# Kanaloa_v2_0_0_Motor.net
KiCad netlist of a schematic drawn in Altium Designer
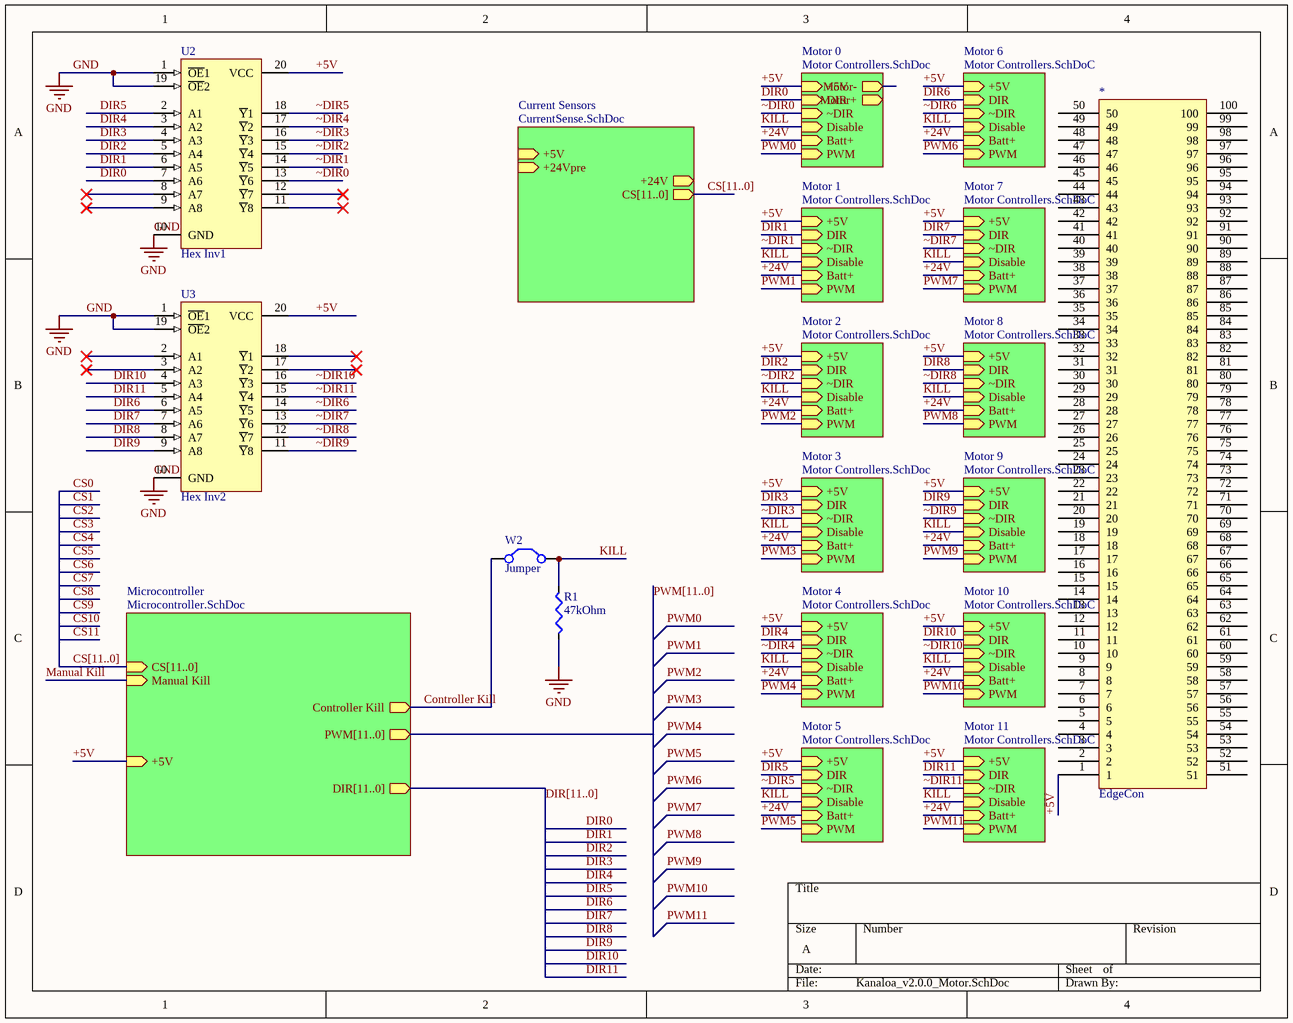
[diagram p0: Kanaloa_v2.0.0_Motor.SchDoc]

(export (version "E")
  (design (tool "Eeschema 10.0.6"))
  (components
    (comp (ref "*")
      (value "EdgeCon")
      (footprint "5645235-3 CON")
      (libsource (lib "Kanaloa_v2.0.0_Motor") (part "EdgeCon"))
    )
    (comp (ref "R1")
      (value "47kOhm")
      (footprint "R 1210 (3225) RESISTOR")
      (description "Resistor")
      (libsource (lib "PassiveComponents") (part "Resistor"))
    )
    (comp (ref "U2")
      (value "Hex Inv1")
      (footprint "DW020_N")
      (description "Octal Buffer and Line Driver with 3-State Outputs")
      (fields (field (name "PUBLISHER") "Altium Limited"))
      (libsource (lib "TI Logic Buffer Line Driver") (part "SN74HCT540DW"))
    )
    (comp (ref "U3")
      (value "Hex Inv2")
      (footprint "DW020_N")
      (description "Octal Buffer and Line Driver with 3-State Outputs")
      (fields (field (name "PUBLISHER") "Altium Limited"))
      (libsource (lib "TI Logic Buffer Line Driver") (part "SN74HCT540DW"))
    )
    (comp (ref "W2")
      (value "Jumper")
      (footprint "RAD-0.2")
      (description "Jumper Wire")
      (fields (field (name "PUBLISHER") "Altium Limited"))
      (libsource (lib "Miscellaneous Devices") (part "Jumper"))
    )
  )
  (nets
    (net (code "1") (name "/+5V") (class "Default")
      (node (ref "*") (pin "1") (pinfunction "1_1") (pintype "passive"))
      (node (ref "U2") (pin "20") (pinfunction "VCC_20") (pintype "power_in"))
      (node (ref "U3") (pin "20") (pinfunction "VCC_20") (pintype "power_in"))
    )
    (net (code "19") (name "/Controller Kill") (class "Default")
      (node (ref "W2") (pin "1") (pinfunction "C1_1") (pintype "passive"))
    )
    (net (code "20") (name "/DIR0") (class "Default")
      (node (ref "U2") (pin "7") (pinfunction "A6_7") (pintype "input"))
    )
    (net (code "21") (name "/DIR1") (class "Default")
      (node (ref "U2") (pin "6") (pinfunction "A5_6") (pintype "input"))
    )
    (net (code "22") (name "/DIR2") (class "Default")
      (node (ref "U2") (pin "5") (pinfunction "A4_5") (pintype "input"))
    )
    (net (code "23") (name "/DIR3") (class "Default")
      (node (ref "U2") (pin "4") (pinfunction "A3_4") (pintype "input"))
    )
    (net (code "24") (name "/DIR4") (class "Default")
      (node (ref "U2") (pin "3") (pinfunction "A2_3") (pintype "input"))
    )
    (net (code "25") (name "/DIR5") (class "Default")
      (node (ref "U2") (pin "2") (pinfunction "A1_2") (pintype "input"))
    )
    (net (code "26") (name "/DIR6") (class "Default")
      (node (ref "U3") (pin "6") (pinfunction "A5_6") (pintype "input"))
    )
    (net (code "27") (name "/DIR7") (class "Default")
      (node (ref "U3") (pin "7") (pinfunction "A6_7") (pintype "input"))
    )
    (net (code "28") (name "/DIR8") (class "Default")
      (node (ref "U3") (pin "8") (pinfunction "A7_8") (pintype "input"))
    )
    (net (code "29") (name "/DIR9") (class "Default")
      (node (ref "U3") (pin "9") (pinfunction "A8_9") (pintype "input"))
    )
    (net (code "30") (name "/DIR10") (class "Default")
      (node (ref "U3") (pin "4") (pinfunction "A3_4") (pintype "input"))
    )
    (net (code "31") (name "/DIR11") (class "Default")
      (node (ref "U3") (pin "5") (pinfunction "A4_5") (pintype "input"))
    )
    (net (code "33") (name "/KILL") (class "Default")
      (node (ref "R1") (pin "2") (pinfunction "2_2") (pintype "passive"))
      (node (ref "W2") (pin "2") (pinfunction "C2_2") (pintype "passive"))
    )
    (net (code "50") (name "/~DIR0") (class "Default")
      (node (ref "U2") (pin "13") (pinfunction "~{Y}6_13") (pintype "tri_state"))
    )
    (net (code "51") (name "/~DIR1") (class "Default")
      (node (ref "U2") (pin "14") (pinfunction "~{Y}5_14") (pintype "tri_state"))
    )
    (net (code "52") (name "/~DIR2") (class "Default")
      (node (ref "U2") (pin "15") (pinfunction "~{Y}4_15") (pintype "tri_state"))
    )
    (net (code "53") (name "/~DIR3") (class "Default")
      (node (ref "U2") (pin "16") (pinfunction "~{Y}3_16") (pintype "tri_state"))
    )
    (net (code "54") (name "/~DIR4") (class "Default")
      (node (ref "U2") (pin "17") (pinfunction "~{Y}2_17") (pintype "tri_state"))
    )
    (net (code "55") (name "/~DIR5") (class "Default")
      (node (ref "U2") (pin "18") (pinfunction "~{Y}1_18") (pintype "tri_state"))
    )
    (net (code "56") (name "/~DIR6") (class "Default")
      (node (ref "U3") (pin "14") (pinfunction "~{Y}5_14") (pintype "tri_state"))
    )
    (net (code "57") (name "/~DIR7") (class "Default")
      (node (ref "U3") (pin "13") (pinfunction "~{Y}6_13") (pintype "tri_state"))
    )
    (net (code "58") (name "/~DIR8") (class "Default")
      (node (ref "U3") (pin "12") (pinfunction "~{Y}7_12") (pintype "tri_state"))
    )
    (net (code "59") (name "/~DIR9") (class "Default")
      (node (ref "U3") (pin "11") (pinfunction "~{Y}8_11") (pintype "tri_state"))
    )
    (net (code "60") (name "/~DIR10") (class "Default")
      (node (ref "U3") (pin "16") (pinfunction "~{Y}3_16") (pintype "tri_state"))
    )
    (net (code "61") (name "/~DIR11") (class "Default")
      (node (ref "U3") (pin "15") (pinfunction "~{Y}4_15") (pintype "tri_state"))
    )
    (net (code "62") (name "GND") (class "Default")
      (node (ref "R1") (pin "1") (pinfunction "1_1") (pintype "passive"))
      (node (ref "U2") (pin "1") (pinfunction "~{OE}1_1") (pintype "input"))
      (node (ref "U2") (pin "10") (pinfunction "GND_10") (pintype "power_in"))
      (node (ref "U2") (pin "19") (pinfunction "~{OE}2_19") (pintype "input"))
      (node (ref "U3") (pin "1") (pinfunction "~{OE}1_1") (pintype "input"))
      (node (ref "U3") (pin "10") (pinfunction "GND_10") (pintype "power_in"))
      (node (ref "U3") (pin "19") (pinfunction "~{OE}2_19") (pintype "input"))
    )
    (net (code "63") (name "unconnected-(*-Pad2)") (class "Default")
      (node (ref "*") (pin "2") (pinfunction "2_2") (pintype "passive"))
    )
    (net (code "64") (name "unconnected-(*-Pad3)") (class "Default")
      (node (ref "*") (pin "3") (pinfunction "3_3") (pintype "passive"))
    )
    (net (code "65") (name "unconnected-(*-Pad4)") (class "Default")
      (node (ref "*") (pin "4") (pinfunction "4_4") (pintype "passive"))
    )
    (net (code "66") (name "unconnected-(*-Pad5)") (class "Default")
      (node (ref "*") (pin "5") (pinfunction "5_5") (pintype "passive"))
    )
    (net (code "67") (name "unconnected-(*-Pad6)") (class "Default")
      (node (ref "*") (pin "6") (pinfunction "6_6") (pintype "passive"))
    )
    (net (code "68") (name "unconnected-(*-Pad7)") (class "Default")
      (node (ref "*") (pin "7") (pinfunction "7_7") (pintype "passive"))
    )
    (net (code "69") (name "unconnected-(*-Pad8)") (class "Default")
      (node (ref "*") (pin "8") (pinfunction "8_8") (pintype "passive"))
    )
    (net (code "70") (name "unconnected-(*-Pad9)") (class "Default")
      (node (ref "*") (pin "9") (pinfunction "9_9") (pintype "passive"))
    )
    (net (code "71") (name "unconnected-(*-Pad10)") (class "Default")
      (node (ref "*") (pin "10") (pinfunction "10_10") (pintype "passive"))
    )
    (net (code "72") (name "unconnected-(*-Pad11)") (class "Default")
      (node (ref "*") (pin "11") (pinfunction "11_11") (pintype "passive"))
    )
    (net (code "73") (name "unconnected-(*-Pad12)") (class "Default")
      (node (ref "*") (pin "12") (pinfunction "12_12") (pintype "passive"))
    )
    (net (code "74") (name "unconnected-(*-Pad13)") (class "Default")
      (node (ref "*") (pin "13") (pinfunction "13_13") (pintype "passive"))
    )
    (net (code "75") (name "unconnected-(*-Pad14)") (class "Default")
      (node (ref "*") (pin "14") (pinfunction "14_14") (pintype "passive"))
    )
    (net (code "76") (name "unconnected-(*-Pad15)") (class "Default")
      (node (ref "*") (pin "15") (pinfunction "15_15") (pintype "passive"))
    )
    (net (code "77") (name "unconnected-(*-Pad16)") (class "Default")
      (node (ref "*") (pin "16") (pinfunction "16_16") (pintype "passive"))
    )
    (net (code "78") (name "unconnected-(*-Pad17)") (class "Default")
      (node (ref "*") (pin "17") (pinfunction "17_17") (pintype "passive"))
    )
    (net (code "79") (name "unconnected-(*-Pad18)") (class "Default")
      (node (ref "*") (pin "18") (pinfunction "18_18") (pintype "passive"))
    )
    (net (code "80") (name "unconnected-(*-Pad19)") (class "Default")
      (node (ref "*") (pin "19") (pinfunction "19_19") (pintype "passive"))
    )
    (net (code "81") (name "unconnected-(*-Pad20)") (class "Default")
      (node (ref "*") (pin "20") (pinfunction "20_20") (pintype "passive"))
    )
    (net (code "82") (name "unconnected-(*-Pad21)") (class "Default")
      (node (ref "*") (pin "21") (pinfunction "21_21") (pintype "passive"))
    )
    (net (code "83") (name "unconnected-(*-Pad22)") (class "Default")
      (node (ref "*") (pin "22") (pinfunction "22_22") (pintype "passive"))
    )
    (net (code "84") (name "unconnected-(*-Pad23)") (class "Default")
      (node (ref "*") (pin "23") (pinfunction "23_23") (pintype "passive"))
    )
    (net (code "85") (name "unconnected-(*-Pad24)") (class "Default")
      (node (ref "*") (pin "24") (pinfunction "24_24") (pintype "passive"))
    )
    (net (code "86") (name "unconnected-(*-Pad25)") (class "Default")
      (node (ref "*") (pin "25") (pinfunction "25_25") (pintype "passive"))
    )
    (net (code "87") (name "unconnected-(*-Pad26)") (class "Default")
      (node (ref "*") (pin "26") (pinfunction "26_26") (pintype "passive"))
    )
    (net (code "88") (name "unconnected-(*-Pad27)") (class "Default")
      (node (ref "*") (pin "27") (pinfunction "27_27") (pintype "passive"))
    )
    (net (code "89") (name "unconnected-(*-Pad28)") (class "Default")
      (node (ref "*") (pin "28") (pinfunction "28_28") (pintype "passive"))
    )
    (net (code "90") (name "unconnected-(*-Pad29)") (class "Default")
      (node (ref "*") (pin "29") (pinfunction "29_29") (pintype "passive"))
    )
    (net (code "91") (name "unconnected-(*-Pad30)") (class "Default")
      (node (ref "*") (pin "30") (pinfunction "30_30") (pintype "passive"))
    )
    (net (code "92") (name "unconnected-(*-Pad31)") (class "Default")
      (node (ref "*") (pin "31") (pinfunction "31_31") (pintype "passive"))
    )
    (net (code "93") (name "unconnected-(*-Pad32)") (class "Default")
      (node (ref "*") (pin "32") (pinfunction "32_32") (pintype "passive"))
    )
    (net (code "94") (name "unconnected-(*-Pad33)") (class "Default")
      (node (ref "*") (pin "33") (pinfunction "33_33") (pintype "passive"))
    )
    (net (code "95") (name "unconnected-(*-Pad34)") (class "Default")
      (node (ref "*") (pin "34") (pinfunction "34_34") (pintype "passive"))
    )
    (net (code "96") (name "unconnected-(*-Pad35)") (class "Default")
      (node (ref "*") (pin "35") (pinfunction "35_35") (pintype "passive"))
    )
    (net (code "97") (name "unconnected-(*-Pad36)") (class "Default")
      (node (ref "*") (pin "36") (pinfunction "36_36") (pintype "passive"))
    )
    (net (code "98") (name "unconnected-(*-Pad37)") (class "Default")
      (node (ref "*") (pin "37") (pinfunction "37_37") (pintype "passive"))
    )
    (net (code "99") (name "unconnected-(*-Pad38)") (class "Default")
      (node (ref "*") (pin "38") (pinfunction "38_38") (pintype "passive"))
    )
    (net (code "100") (name "unconnected-(*-Pad39)") (class "Default")
      (node (ref "*") (pin "39") (pinfunction "39_39") (pintype "passive"))
    )
    (net (code "101") (name "unconnected-(*-Pad40)") (class "Default")
      (node (ref "*") (pin "40") (pinfunction "40_40") (pintype "passive"))
    )
    (net (code "102") (name "unconnected-(*-Pad41)") (class "Default")
      (node (ref "*") (pin "41") (pinfunction "41_41") (pintype "passive"))
    )
    (net (code "103") (name "unconnected-(*-Pad42)") (class "Default")
      (node (ref "*") (pin "42") (pinfunction "42_42") (pintype "passive"))
    )
    (net (code "104") (name "unconnected-(*-Pad43)") (class "Default")
      (node (ref "*") (pin "43") (pinfunction "43_43") (pintype "passive"))
    )
    (net (code "105") (name "unconnected-(*-Pad44)") (class "Default")
      (node (ref "*") (pin "44") (pinfunction "44_44") (pintype "passive"))
    )
    (net (code "106") (name "unconnected-(*-Pad45)") (class "Default")
      (node (ref "*") (pin "45") (pinfunction "45_45") (pintype "passive"))
    )
    (net (code "107") (name "unconnected-(*-Pad46)") (class "Default")
      (node (ref "*") (pin "46") (pinfunction "46_46") (pintype "passive"))
    )
    (net (code "108") (name "unconnected-(*-Pad47)") (class "Default")
      (node (ref "*") (pin "47") (pinfunction "47_47") (pintype "passive"))
    )
    (net (code "109") (name "unconnected-(*-Pad48)") (class "Default")
      (node (ref "*") (pin "48") (pinfunction "48_48") (pintype "passive"))
    )
    (net (code "110") (name "unconnected-(*-Pad49)") (class "Default")
      (node (ref "*") (pin "49") (pinfunction "49_49") (pintype "passive"))
    )
    (net (code "111") (name "unconnected-(*-Pad50)") (class "Default")
      (node (ref "*") (pin "50") (pinfunction "50_50") (pintype "passive"))
    )
    (net (code "112") (name "unconnected-(*-Pad51)") (class "Default")
      (node (ref "*") (pin "51") (pinfunction "51_51") (pintype "passive"))
    )
    (net (code "113") (name "unconnected-(*-Pad52)") (class "Default")
      (node (ref "*") (pin "52") (pinfunction "52_52") (pintype "passive"))
    )
    (net (code "114") (name "unconnected-(*-Pad53)") (class "Default")
      (node (ref "*") (pin "53") (pinfunction "53_53") (pintype "passive"))
    )
    (net (code "115") (name "unconnected-(*-Pad54)") (class "Default")
      (node (ref "*") (pin "54") (pinfunction "54_54") (pintype "passive"))
    )
    (net (code "116") (name "unconnected-(*-Pad55)") (class "Default")
      (node (ref "*") (pin "55") (pinfunction "55_55") (pintype "passive"))
    )
    (net (code "117") (name "unconnected-(*-Pad56)") (class "Default")
      (node (ref "*") (pin "56") (pinfunction "56_56") (pintype "passive"))
    )
    (net (code "118") (name "unconnected-(*-Pad57)") (class "Default")
      (node (ref "*") (pin "57") (pinfunction "57_57") (pintype "passive"))
    )
    (net (code "119") (name "unconnected-(*-Pad58)") (class "Default")
      (node (ref "*") (pin "58") (pinfunction "58_58") (pintype "passive"))
    )
    (net (code "120") (name "unconnected-(*-Pad59)") (class "Default")
      (node (ref "*") (pin "59") (pinfunction "59_59") (pintype "passive"))
    )
    (net (code "121") (name "unconnected-(*-Pad60)") (class "Default")
      (node (ref "*") (pin "60") (pinfunction "60_60") (pintype "passive"))
    )
    (net (code "122") (name "unconnected-(*-Pad61)") (class "Default")
      (node (ref "*") (pin "61") (pinfunction "61_61") (pintype "passive"))
    )
    (net (code "123") (name "unconnected-(*-Pad62)") (class "Default")
      (node (ref "*") (pin "62") (pinfunction "62_62") (pintype "passive"))
    )
    (net (code "124") (name "unconnected-(*-Pad63)") (class "Default")
      (node (ref "*") (pin "63") (pinfunction "63_63") (pintype "passive"))
    )
    (net (code "125") (name "unconnected-(*-Pad64)") (class "Default")
      (node (ref "*") (pin "64") (pinfunction "64_64") (pintype "passive"))
    )
    (net (code "126") (name "unconnected-(*-Pad65)") (class "Default")
      (node (ref "*") (pin "65") (pinfunction "65_65") (pintype "passive"))
    )
    (net (code "127") (name "unconnected-(*-Pad66)") (class "Default")
      (node (ref "*") (pin "66") (pinfunction "66_66") (pintype "passive"))
    )
    (net (code "128") (name "unconnected-(*-Pad67)") (class "Default")
      (node (ref "*") (pin "67") (pinfunction "67_67") (pintype "passive"))
    )
    (net (code "129") (name "unconnected-(*-Pad68)") (class "Default")
      (node (ref "*") (pin "68") (pinfunction "68_68") (pintype "passive"))
    )
    (net (code "130") (name "unconnected-(*-Pad69)") (class "Default")
      (node (ref "*") (pin "69") (pinfunction "69_69") (pintype "passive"))
    )
    (net (code "131") (name "unconnected-(*-Pad70)") (class "Default")
      (node (ref "*") (pin "70") (pinfunction "70_70") (pintype "passive"))
    )
    (net (code "132") (name "unconnected-(*-Pad71)") (class "Default")
      (node (ref "*") (pin "71") (pinfunction "71_71") (pintype "passive"))
    )
    (net (code "133") (name "unconnected-(*-Pad72)") (class "Default")
      (node (ref "*") (pin "72") (pinfunction "72_72") (pintype "passive"))
    )
    (net (code "134") (name "unconnected-(*-Pad73)") (class "Default")
      (node (ref "*") (pin "73") (pinfunction "73_73") (pintype "passive"))
    )
    (net (code "135") (name "unconnected-(*-Pad74)") (class "Default")
      (node (ref "*") (pin "74") (pinfunction "74_74") (pintype "passive"))
    )
    (net (code "136") (name "unconnected-(*-Pad75)") (class "Default")
      (node (ref "*") (pin "75") (pinfunction "75_75") (pintype "passive"))
    )
    (net (code "137") (name "unconnected-(*-Pad76)") (class "Default")
      (node (ref "*") (pin "76") (pinfunction "76_76") (pintype "passive"))
    )
    (net (code "138") (name "unconnected-(*-Pad77)") (class "Default")
      (node (ref "*") (pin "77") (pinfunction "77_77") (pintype "passive"))
    )
    (net (code "139") (name "unconnected-(*-Pad78)") (class "Default")
      (node (ref "*") (pin "78") (pinfunction "78_78") (pintype "passive"))
    )
    (net (code "140") (name "unconnected-(*-Pad79)") (class "Default")
      (node (ref "*") (pin "79") (pinfunction "79_79") (pintype "passive"))
    )
    (net (code "141") (name "unconnected-(*-Pad80)") (class "Default")
      (node (ref "*") (pin "80") (pinfunction "80_80") (pintype "passive"))
    )
    (net (code "142") (name "unconnected-(*-Pad81)") (class "Default")
      (node (ref "*") (pin "81") (pinfunction "81_81") (pintype "passive"))
    )
    (net (code "143") (name "unconnected-(*-Pad82)") (class "Default")
      (node (ref "*") (pin "82") (pinfunction "82_82") (pintype "passive"))
    )
    (net (code "144") (name "unconnected-(*-Pad83)") (class "Default")
      (node (ref "*") (pin "83") (pinfunction "83_83") (pintype "passive"))
    )
    (net (code "145") (name "unconnected-(*-Pad84)") (class "Default")
      (node (ref "*") (pin "84") (pinfunction "84_84") (pintype "passive"))
    )
    (net (code "146") (name "unconnected-(*-Pad85)") (class "Default")
      (node (ref "*") (pin "85") (pinfunction "85_85") (pintype "passive"))
    )
    (net (code "147") (name "unconnected-(*-Pad86)") (class "Default")
      (node (ref "*") (pin "86") (pinfunction "86_86") (pintype "passive"))
    )
    (net (code "148") (name "unconnected-(*-Pad87)") (class "Default")
      (node (ref "*") (pin "87") (pinfunction "87_87") (pintype "passive"))
    )
    (net (code "149") (name "unconnected-(*-Pad88)") (class "Default")
      (node (ref "*") (pin "88") (pinfunction "88_88") (pintype "passive"))
    )
    (net (code "150") (name "unconnected-(*-Pad89)") (class "Default")
      (node (ref "*") (pin "89") (pinfunction "89_89") (pintype "passive"))
    )
    (net (code "151") (name "unconnected-(*-Pad90)") (class "Default")
      (node (ref "*") (pin "90") (pinfunction "90_90") (pintype "passive"))
    )
    (net (code "152") (name "unconnected-(*-Pad91)") (class "Default")
      (node (ref "*") (pin "91") (pinfunction "91_91") (pintype "passive"))
    )
    (net (code "153") (name "unconnected-(*-Pad92)") (class "Default")
      (node (ref "*") (pin "92") (pinfunction "92_92") (pintype "passive"))
    )
    (net (code "154") (name "unconnected-(*-Pad93)") (class "Default")
      (node (ref "*") (pin "93") (pinfunction "93_93") (pintype "passive"))
    )
    (net (code "155") (name "unconnected-(*-Pad94)") (class "Default")
      (node (ref "*") (pin "94") (pinfunction "94_94") (pintype "passive"))
    )
    (net (code "156") (name "unconnected-(*-Pad95)") (class "Default")
      (node (ref "*") (pin "95") (pinfunction "95_95") (pintype "passive"))
    )
    (net (code "157") (name "unconnected-(*-Pad96)") (class "Default")
      (node (ref "*") (pin "96") (pinfunction "96_96") (pintype "passive"))
    )
    (net (code "158") (name "unconnected-(*-Pad97)") (class "Default")
      (node (ref "*") (pin "97") (pinfunction "97_97") (pintype "passive"))
    )
    (net (code "159") (name "unconnected-(*-Pad98)") (class "Default")
      (node (ref "*") (pin "98") (pinfunction "98_98") (pintype "passive"))
    )
    (net (code "160") (name "unconnected-(*-Pad99)") (class "Default")
      (node (ref "*") (pin "99") (pinfunction "99_99") (pintype "passive"))
    )
    (net (code "161") (name "unconnected-(*-Pad100)") (class "Default")
      (node (ref "*") (pin "100") (pinfunction "100_100") (pintype "passive"))
    )
    (net (code "162") (name "unconnected-(U2-A7-Pad8)") (class "Default")
      (node (ref "U2") (pin "8") (pinfunction "A7_8") (pintype "input+no_connect"))
    )
    (net (code "163") (name "unconnected-(U2-A8-Pad9)") (class "Default")
      (node (ref "U2") (pin "9") (pinfunction "A8_9") (pintype "input+no_connect"))
    )
    (net (code "164") (name "unconnected-(U2-~{Y}7-Pad12)") (class "Default")
      (node (ref "U2") (pin "12") (pinfunction "~{Y}7_12") (pintype "tri_state+no_connect"))
    )
    (net (code "165") (name "unconnected-(U2-~{Y}8-Pad11)") (class "Default")
      (node (ref "U2") (pin "11") (pinfunction "~{Y}8_11") (pintype "tri_state+no_connect"))
    )
    (net (code "166") (name "unconnected-(U3-A1-Pad2)") (class "Default")
      (node (ref "U3") (pin "2") (pinfunction "A1_2") (pintype "input+no_connect"))
    )
    (net (code "167") (name "unconnected-(U3-A2-Pad3)") (class "Default")
      (node (ref "U3") (pin "3") (pinfunction "A2_3") (pintype "input+no_connect"))
    )
    (net (code "168") (name "unconnected-(U3-~{Y}1-Pad18)") (class "Default")
      (node (ref "U3") (pin "18") (pinfunction "~{Y}1_18") (pintype "tri_state+no_connect"))
    )
    (net (code "169") (name "unconnected-(U3-~{Y}2-Pad17)") (class "Default")
      (node (ref "U3") (pin "17") (pinfunction "~{Y}2_17") (pintype "tri_state+no_connect"))
    )
  )
)
